# Board_V07A.net
KiCad netlist of a schematic drawn in EAGLE
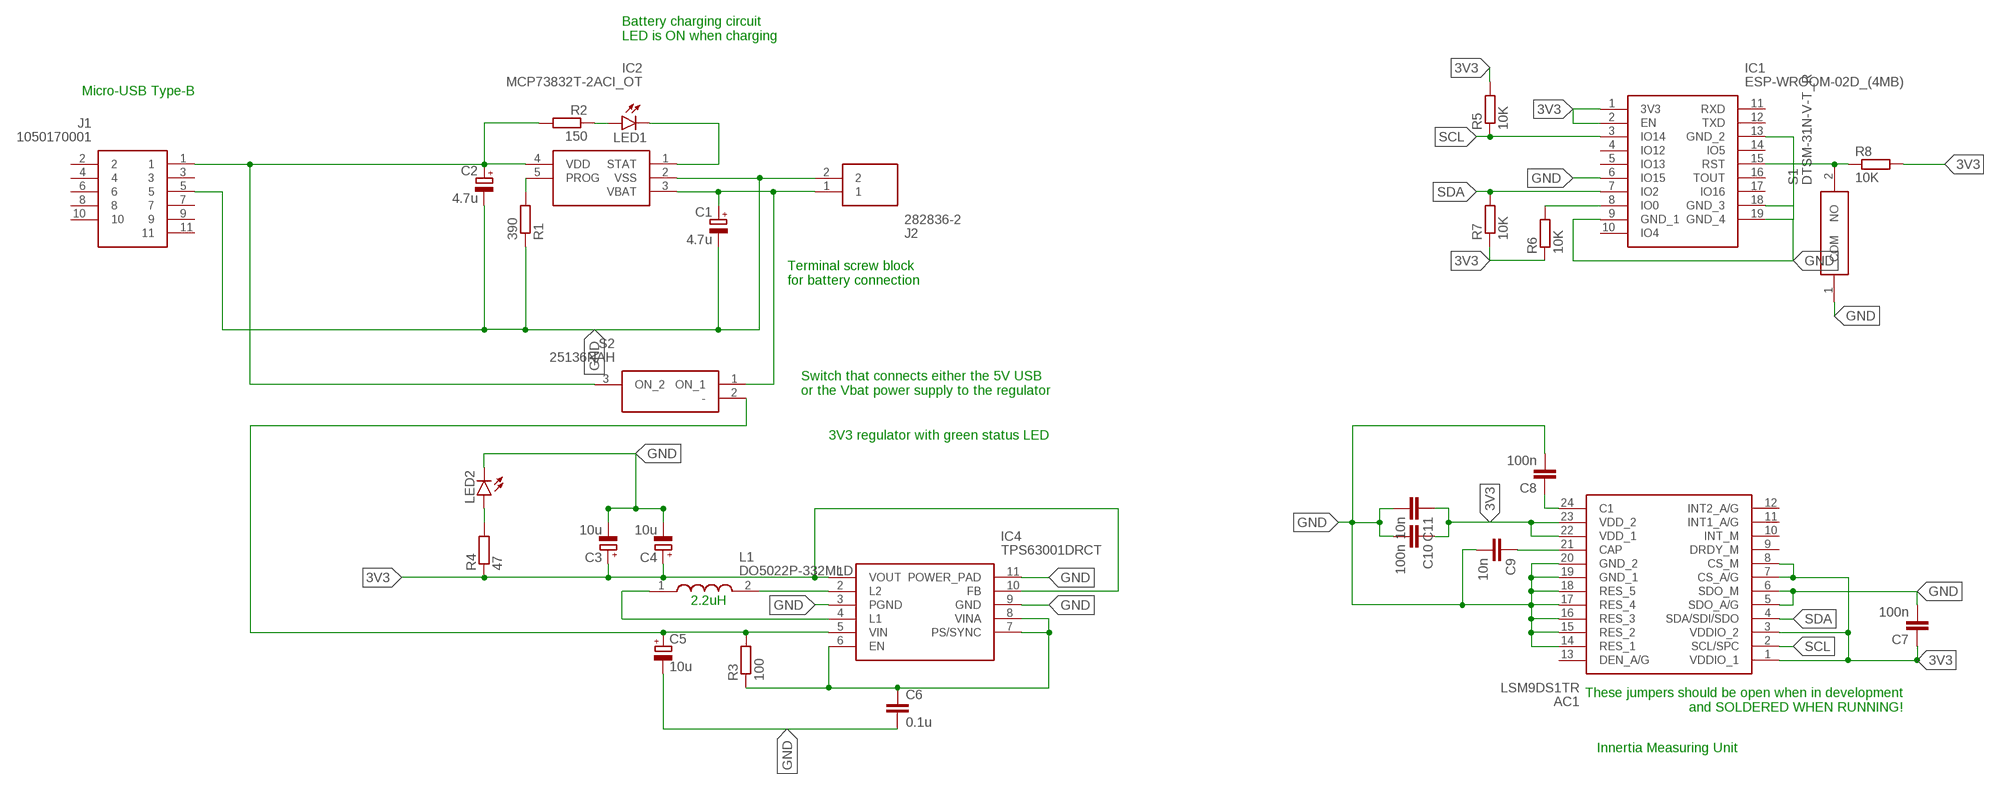
[diagram p0: schematic, sheet 1]

(export (version "E")
  (design (tool "Eeschema 10.0.6"))
  (components
    (comp (ref "AC1")
      (value "LSM9DS1TR")
      (footprint "eagle-import:LGA-24L(3X3.5X1MM)")
      (fields (field (name "MOUSER_PART_NUMBER") "511-LSM9DS1TR") (field (name "RS_PART_NUMBER") "1660908"))
      (libsource (lib "eagle-import") (part "LSM9DS1TR"))
    )
    (comp (ref "C1")
      (value "4.7u")
      (footprint "eagle-import:D_7343-31R")
      (libsource (lib "eagle-import") (part "CPOL-EUD/7343-31R"))
    )
    (comp (ref "C2")
      (value "4.7u")
      (footprint "eagle-import:D_7343-31R")
      (libsource (lib "eagle-import") (part "CPOL-EUD/7343-31R"))
    )
    (comp (ref "C3")
      (value "10u")
      (footprint "eagle-import:D_7343-31R")
      (libsource (lib "eagle-import") (part "CPOL-EUD/7343-31R"))
    )
    (comp (ref "C4")
      (value "10u")
      (footprint "eagle-import:D_7343-31R")
      (libsource (lib "eagle-import") (part "CPOL-EUD/7343-31R"))
    )
    (comp (ref "C5")
      (value "10u")
      (footprint "eagle-import:D_7343-31R")
      (libsource (lib "eagle-import") (part "CPOL-EUD/7343-31R"))
    )
    (comp (ref "C6")
      (value "0.1u")
      (footprint "eagle-import:C0402")
      (libsource (lib "eagle-import") (part "C-EUC0402"))
    )
    (comp (ref "C7")
      (value "100n")
      (footprint "eagle-import:C0805")
      (libsource (lib "eagle-import") (part "C-EUC0805"))
    )
    (comp (ref "C8")
      (value "100n")
      (footprint "eagle-import:C0805")
      (libsource (lib "eagle-import") (part "C-EUC0805"))
    )
    (comp (ref "C9")
      (value "10n")
      (footprint "eagle-import:C0805")
      (libsource (lib "eagle-import") (part "C-EUC0805"))
    )
    (comp (ref "C10")
      (value "100n")
      (footprint "eagle-import:C0805")
      (libsource (lib "eagle-import") (part "C-EUC0805"))
    )
    (comp (ref "C11")
      (value "10n")
      (footprint "eagle-import:C0805")
      (libsource (lib "eagle-import") (part "C-EUC0805"))
    )
    (comp (ref "IC1")
      (value "ESP-WROOM-02D_(4MB)")
      (footprint "eagle-import:ESPWROOM02D")
      (fields
        (field (name "MANUFACTURER_PART_NUMBER") "ESP-WROOM-02D (4MB)")
        (field (name "MOUSER_PART_NUMBER") "356-ESPWROOM02D(4MB)")
      )
      (libsource (lib "eagle-import") (part "ESP-WROOM-02D_(4MB)"))
    )
    (comp (ref "IC2")
      (value "MCP73832T-2ACI_OT")
      (footprint "eagle-import:SOT95P270X145-5N")
      (fields
        (field (name "MANUFACTURER_PART_NUMBER") "MCP73832T-2ACI/OT")
        (field (name "MOUSER_PART_NUMBER") "579-MCP73832T-2ACIOT")
        (field (name "RS_PART_NUMBER") "9122897")
      )
      (libsource (lib "eagle-import") (part "MCP73832T-2ACI_OT"))
    )
    (comp (ref "IC4")
      (value "TPS63001DRCT")
      (footprint "eagle-import:SON50P300X300X100-11N")
      (fields (field (name "RS_PART_NUMBER") "7968405"))
      (libsource (lib "eagle-import") (part "TPS63001DRCT"))
    )
    (comp (ref "J1")
      (value "1050170001")
      (footprint "eagle-import:MICROUSB-BTYPE")
      (libsource (lib "eagle-import") (part "1050170001"))
    )
    (comp (ref "J2")
      (value "282836-2")
      (footprint "eagle-import:SHDR2W100P0X500_1X2_1000X820X1")
      (fields (field (name "MOUSER_PART_NUMBER") "571-2828362") (field (name "RS_PART_NUMBER") "1354983"))
      (libsource (lib "eagle-import") (part "282836-2"))
    )
    (comp (ref "L1")
      (value "DO5022P-332MLD")
      (footprint "eagle-import:DO5022P-104MLD")
      (fields (field (name "MOUSER_PART_NUMBER") "994-DO5022P-332MLD"))
      (libsource (lib "eagle-import") (part "DO5022P-332MLD"))
    )
    (comp (ref "LED1")
      (value "LED5MM")
      (footprint "eagle-import:LED5MM")
      (libsource (lib "eagle-import") (part "LED5MM"))
    )
    (comp (ref "LED2")
      (value "LED5MM")
      (footprint "eagle-import:LED5MM")
      (libsource (lib "eagle-import") (part "LED5MM"))
    )
    (comp (ref "R1")
      (value "390")
      (footprint "eagle-import:R0805")
      (libsource (lib "eagle-import") (part "R-EU_R0805"))
    )
    (comp (ref "R2")
      (value "150")
      (footprint "eagle-import:R0805")
      (libsource (lib "eagle-import") (part "R-EU_R0805"))
    )
    (comp (ref "R3")
      (value "100")
      (footprint "eagle-import:R0805")
      (libsource (lib "eagle-import") (part "R-EU_R0805"))
    )
    (comp (ref "R4")
      (value "47")
      (footprint "eagle-import:R0805")
      (libsource (lib "eagle-import") (part "R-EU_R0805"))
    )
    (comp (ref "R5")
      (value "10K")
      (footprint "eagle-import:R0805")
      (libsource (lib "eagle-import") (part "R-EU_R0805"))
    )
    (comp (ref "R6")
      (value "10K")
      (footprint "eagle-import:R0805")
      (libsource (lib "eagle-import") (part "R-EU_R0805"))
    )
    (comp (ref "R7")
      (value "10K")
      (footprint "eagle-import:R0805")
      (libsource (lib "eagle-import") (part "R-EU_R0805"))
    )
    (comp (ref "R8")
      (value "10K")
      (footprint "eagle-import:R0805")
      (libsource (lib "eagle-import") (part "R-EU_R0805"))
    )
    (comp (ref "S1")
      (value "DTSM-31N-V-T_R")
      (footprint "eagle-import:DTSM32NVTR")
      (fields
        (field (name "MANUFACTURER_PART_NUMBER") "DTSM-31N-V-T/R")
        (field (name "MOUSER_PART_NUMBER") "113-DTSM31NVTR")
      )
      (libsource (lib "eagle-import") (part "DTSM-31N-V-T_R"))
    )
    (comp (ref "S2")
      (value "25136NAH")
      (footprint "eagle-import:25136NAH")
      (fields (field (name "MOUSER_PART_NUMBER") "642-25136NAH") (field (name "RS_PART_NUMBER") "0339673A"))
      (libsource (lib "eagle-import") (part "25136NAH"))
    )
  )
  (nets
    (net (code "1") (name "3V3") (class "Default")
      (node (ref "AC1") (pin "1") (pinfunction "VDDIO_1_1") (pintype "power_in"))
      (node (ref "AC1") (pin "22") (pinfunction "VDD_1_22") (pintype "power_in"))
      (node (ref "AC1") (pin "23") (pinfunction "VDD_2_23") (pintype "power_in"))
      (node (ref "AC1") (pin "3") (pinfunction "VDDIO_2_3") (pintype "power_in"))
      (node (ref "AC1") (pin "7") (pinfunction "CS_A/G_7") (pintype "bidirectional"))
      (node (ref "AC1") (pin "8") (pinfunction "CS_M_8") (pintype "bidirectional"))
      (node (ref "C10") (pin "1") (pinfunction "1_1") (pintype "passive"))
      (node (ref "C11") (pin "1") (pinfunction "1_1") (pintype "passive"))
      (node (ref "C3") (pin "+") (pinfunction "+_+") (pintype "passive"))
      (node (ref "C4") (pin "+") (pinfunction "+_+") (pintype "passive"))
      (node (ref "C7") (pin "1") (pinfunction "1_1") (pintype "passive"))
      (node (ref "IC1") (pin "1") (pinfunction "3V3_1") (pintype "bidirectional"))
      (node (ref "IC1") (pin "2") (pinfunction "EN_2") (pintype "bidirectional"))
      (node (ref "IC4") (pin "1") (pinfunction "VOUT_1") (pintype "bidirectional"))
      (node (ref "IC4") (pin "10") (pinfunction "FB_10") (pintype "bidirectional"))
      (node (ref "R4") (pin "1") (pinfunction "1_1") (pintype "passive"))
      (node (ref "R5") (pin "2") (pinfunction "2_2") (pintype "passive"))
      (node (ref "R6") (pin "1") (pinfunction "1_1") (pintype "passive"))
      (node (ref "R7") (pin "1") (pinfunction "1_1") (pintype "passive"))
      (node (ref "R8") (pin "2") (pinfunction "2_2") (pintype "passive"))
    )
    (net (code "2") (name "GND") (class "Default")
      (node (ref "AC1") (pin "14") (pinfunction "RES_1_14") (pintype "power_in"))
      (node (ref "AC1") (pin "15") (pinfunction "RES_2_15") (pintype "power_in"))
      (node (ref "AC1") (pin "16") (pinfunction "RES_3_16") (pintype "power_in"))
      (node (ref "AC1") (pin "17") (pinfunction "RES_4_17") (pintype "power_in"))
      (node (ref "AC1") (pin "18") (pinfunction "RES_5_18") (pintype "power_in"))
      (node (ref "AC1") (pin "19") (pinfunction "GND_1_19") (pintype "power_in"))
      (node (ref "AC1") (pin "20") (pinfunction "GND_2_20") (pintype "power_in"))
      (node (ref "AC1") (pin "5") (pinfunction "SDO_A/G_5") (pintype "output"))
      (node (ref "AC1") (pin "6") (pinfunction "SDO_M_6") (pintype "output"))
      (node (ref "C1") (pin "-") (pinfunction "-_-") (pintype "passive"))
      (node (ref "C10") (pin "2") (pinfunction "2_2") (pintype "passive"))
      (node (ref "C11") (pin "2") (pinfunction "2_2") (pintype "passive"))
      (node (ref "C2") (pin "-") (pinfunction "-_-") (pintype "passive"))
      (node (ref "C3") (pin "-") (pinfunction "-_-") (pintype "passive"))
      (node (ref "C4") (pin "-") (pinfunction "-_-") (pintype "passive"))
      (node (ref "C5") (pin "-") (pinfunction "-_-") (pintype "passive"))
      (node (ref "C6") (pin "2") (pinfunction "2_2") (pintype "passive"))
      (node (ref "C7") (pin "2") (pinfunction "2_2") (pintype "passive"))
      (node (ref "C8") (pin "2") (pinfunction "2_2") (pintype "passive"))
      (node (ref "C9") (pin "2") (pinfunction "2_2") (pintype "passive"))
      (node (ref "IC1") (pin "13") (pinfunction "GND_2_13") (pintype "bidirectional"))
      (node (ref "IC1") (pin "18") (pinfunction "GND_3_18") (pintype "bidirectional"))
      (node (ref "IC1") (pin "19") (pinfunction "GND_4_19") (pintype "bidirectional"))
      (node (ref "IC1") (pin "6") (pinfunction "IO15_6") (pintype "bidirectional"))
      (node (ref "IC1") (pin "9") (pinfunction "GND_1_9") (pintype "bidirectional"))
      (node (ref "IC2") (pin "2") (pinfunction "VSS_2") (pintype "power_in"))
      (node (ref "IC4") (pin "11") (pinfunction "POWER_PAD_11") (pintype "bidirectional"))
      (node (ref "IC4") (pin "3") (pinfunction "PGND_3") (pintype "bidirectional"))
      (node (ref "IC4") (pin "9") (pinfunction "GND_9") (pintype "bidirectional"))
      (node (ref "J1") (pin "5") (pinfunction "5_5") (pintype "bidirectional"))
      (node (ref "J2") (pin "2") (pinfunction "2_2") (pintype "bidirectional"))
      (node (ref "LED2") (pin "K") (pinfunction "C_K") (pintype "passive"))
      (node (ref "R1") (pin "1") (pinfunction "1_1") (pintype "passive"))
      (node (ref "S1") (pin "1") (pinfunction "COM_1") (pintype "bidirectional"))
    )
    (net (code "3") (name "Net-(AC1-C1)") (class "Default")
      (node (ref "AC1") (pin "24") (pinfunction "C1_24") (pintype "bidirectional"))
      (node (ref "C8") (pin "1") (pinfunction "1_1") (pintype "passive"))
    )
    (net (code "4") (name "Net-(AC1-CAP)") (class "Default")
      (node (ref "AC1") (pin "21") (pinfunction "CAP_21") (pintype "power_in"))
      (node (ref "C9") (pin "1") (pinfunction "1_1") (pintype "passive"))
    )
    (net (code "5") (name "Net-(IC1-IO0)") (class "Default")
      (node (ref "IC1") (pin "8") (pinfunction "IO0_8") (pintype "bidirectional"))
      (node (ref "R6") (pin "2") (pinfunction "2_2") (pintype "passive"))
    )
    (net (code "6") (name "Net-(IC1-RST)") (class "Default")
      (node (ref "IC1") (pin "15") (pinfunction "RST_15") (pintype "bidirectional"))
      (node (ref "R8") (pin "1") (pinfunction "1_1") (pintype "passive"))
      (node (ref "S1") (pin "2") (pinfunction "NO_2") (pintype "bidirectional"))
    )
    (net (code "7") (name "Net-(IC2-PROG)") (class "Default")
      (node (ref "IC2") (pin "5") (pinfunction "PROG_5") (pintype "bidirectional"))
      (node (ref "R1") (pin "2") (pinfunction "2_2") (pintype "passive"))
    )
    (net (code "8") (name "Net-(IC2-STAT)") (class "Default")
      (node (ref "IC2") (pin "1") (pinfunction "STAT_1") (pintype "bidirectional"))
      (node (ref "LED1") (pin "K") (pinfunction "C_K") (pintype "passive"))
    )
    (net (code "9") (name "Net-(IC2-VBAT)") (class "Default")
      (node (ref "C1") (pin "+") (pinfunction "+_+") (pintype "passive"))
      (node (ref "IC2") (pin "3") (pinfunction "VBAT_3") (pintype "bidirectional"))
      (node (ref "J2") (pin "1") (pinfunction "1_1") (pintype "bidirectional"))
      (node (ref "S2") (pin "1") (pinfunction "ON_1_1") (pintype "bidirectional"))
    )
    (net (code "10") (name "Net-(IC2-VDD)") (class "Default")
      (node (ref "C2") (pin "+") (pinfunction "+_+") (pintype "passive"))
      (node (ref "IC2") (pin "4") (pinfunction "VDD_4") (pintype "power_in"))
      (node (ref "J1") (pin "1") (pinfunction "1_1") (pintype "bidirectional"))
      (node (ref "R2") (pin "2") (pinfunction "2_2") (pintype "passive"))
      (node (ref "S2") (pin "3") (pinfunction "ON_2_3") (pintype "bidirectional"))
    )
    (net (code "11") (name "Net-(IC4-EN)") (class "Default")
      (node (ref "C6") (pin "1") (pinfunction "1_1") (pintype "passive"))
      (node (ref "IC4") (pin "6") (pinfunction "EN_6") (pintype "bidirectional"))
      (node (ref "IC4") (pin "7") (pinfunction "PS/SYNC_7") (pintype "bidirectional"))
      (node (ref "IC4") (pin "8") (pinfunction "VINA_8") (pintype "bidirectional"))
      (node (ref "R3") (pin "1") (pinfunction "1_1") (pintype "passive"))
    )
    (net (code "12") (name "Net-(IC4-L1)") (class "Default")
      (node (ref "IC4") (pin "4") (pinfunction "L1_4") (pintype "bidirectional"))
      (node (ref "L1") (pin "1") (pinfunction "1_1") (pintype "bidirectional"))
    )
    (net (code "13") (name "Net-(IC4-L2)") (class "Default")
      (node (ref "IC4") (pin "2") (pinfunction "L2_2") (pintype "bidirectional"))
      (node (ref "L1") (pin "2") (pinfunction "2_2") (pintype "bidirectional"))
    )
    (net (code "14") (name "Net-(IC4-VIN)") (class "Default")
      (node (ref "C5") (pin "+") (pinfunction "+_+") (pintype "passive"))
      (node (ref "IC4") (pin "5") (pinfunction "VIN_5") (pintype "bidirectional"))
      (node (ref "R3") (pin "2") (pinfunction "2_2") (pintype "passive"))
      (node (ref "S2") (pin "2") (pinfunction "-_2") (pintype "bidirectional"))
    )
    (net (code "15") (name "Net-(LED1-PadA)") (class "Default")
      (node (ref "LED1") (pin "A") (pinfunction "A_A") (pintype "passive"))
      (node (ref "R2") (pin "1") (pinfunction "1_1") (pintype "passive"))
    )
    (net (code "16") (name "Net-(LED2-PadA)") (class "Default")
      (node (ref "LED2") (pin "A") (pinfunction "A_A") (pintype "passive"))
      (node (ref "R4") (pin "2") (pinfunction "2_2") (pintype "passive"))
    )
    (net (code "17") (name "SCL") (class "Default")
      (node (ref "AC1") (pin "2") (pinfunction "SCL/SPC_2") (pintype "output"))
      (node (ref "IC1") (pin "3") (pinfunction "IO14_3") (pintype "bidirectional"))
      (node (ref "R5") (pin "1") (pinfunction "1_1") (pintype "passive"))
    )
    (net (code "18") (name "SDA") (class "Default")
      (node (ref "AC1") (pin "4") (pinfunction "SDA/SDI/SDO_4") (pintype "bidirectional"))
      (node (ref "IC1") (pin "7") (pinfunction "IO2_7") (pintype "bidirectional"))
      (node (ref "R7") (pin "2") (pinfunction "2_2") (pintype "passive"))
    )
    (net (code "19") (name "unconnected-(AC1-DEN_A{slash}G-Pad13)") (class "Default")
      (node (ref "AC1") (pin "13") (pinfunction "DEN_A/G_13") (pintype "bidirectional"))
    )
    (net (code "20") (name "unconnected-(AC1-DRDY_M-Pad9)") (class "Default")
      (node (ref "AC1") (pin "9") (pinfunction "DRDY_M_9") (pintype "bidirectional"))
    )
    (net (code "21") (name "unconnected-(AC1-INT1_A{slash}G-Pad11)") (class "Default")
      (node (ref "AC1") (pin "11") (pinfunction "INT1_A/G_11") (pintype "bidirectional"))
    )
    (net (code "22") (name "unconnected-(AC1-INT2_A{slash}G-Pad12)") (class "Default")
      (node (ref "AC1") (pin "12") (pinfunction "INT2_A/G_12") (pintype "bidirectional"))
    )
    (net (code "23") (name "unconnected-(AC1-INT_M-Pad10)") (class "Default")
      (node (ref "AC1") (pin "10") (pinfunction "INT_M_10") (pintype "bidirectional"))
    )
    (net (code "24") (name "unconnected-(IC1-IO4-Pad10)") (class "Default")
      (node (ref "IC1") (pin "10") (pinfunction "IO4_10") (pintype "bidirectional"))
    )
    (net (code "25") (name "unconnected-(IC1-IO5-Pad14)") (class "Default")
      (node (ref "IC1") (pin "14") (pinfunction "IO5_14") (pintype "bidirectional"))
    )
    (net (code "26") (name "unconnected-(IC1-IO12-Pad4)") (class "Default")
      (node (ref "IC1") (pin "4") (pinfunction "IO12_4") (pintype "bidirectional"))
    )
    (net (code "27") (name "unconnected-(IC1-IO13-Pad5)") (class "Default")
      (node (ref "IC1") (pin "5") (pinfunction "IO13_5") (pintype "bidirectional"))
    )
    (net (code "28") (name "unconnected-(IC1-IO16-Pad17)") (class "Default")
      (node (ref "IC1") (pin "17") (pinfunction "IO16_17") (pintype "bidirectional"))
    )
    (net (code "29") (name "unconnected-(IC1-RXD-Pad11)") (class "Default")
      (node (ref "IC1") (pin "11") (pinfunction "RXD_11") (pintype "bidirectional"))
    )
    (net (code "30") (name "unconnected-(IC1-TOUT-Pad16)") (class "Default")
      (node (ref "IC1") (pin "16") (pinfunction "TOUT_16") (pintype "bidirectional"))
    )
    (net (code "31") (name "unconnected-(IC1-TXD-Pad12)") (class "Default")
      (node (ref "IC1") (pin "12") (pinfunction "TXD_12") (pintype "bidirectional"))
    )
    (net (code "32") (name "unconnected-(J1-Pad2)") (class "Default")
      (node (ref "J1") (pin "2") (pinfunction "2_2") (pintype "bidirectional"))
    )
    (net (code "33") (name "unconnected-(J1-Pad3)") (class "Default")
      (node (ref "J1") (pin "3") (pinfunction "3_3") (pintype "bidirectional"))
    )
    (net (code "34") (name "unconnected-(J1-Pad4)") (class "Default")
      (node (ref "J1") (pin "4") (pinfunction "4_4") (pintype "bidirectional"))
    )
    (net (code "35") (name "unconnected-(J1-Pad6)") (class "Default")
      (node (ref "J1") (pin "6") (pinfunction "6_6") (pintype "bidirectional"))
    )
    (net (code "36") (name "unconnected-(J1-Pad7)") (class "Default")
      (node (ref "J1") (pin "7") (pinfunction "7_7") (pintype "bidirectional"))
    )
    (net (code "37") (name "unconnected-(J1-Pad8)") (class "Default")
      (node (ref "J1") (pin "8") (pinfunction "8_8") (pintype "bidirectional"))
    )
    (net (code "38") (name "unconnected-(J1-Pad9)") (class "Default")
      (node (ref "J1") (pin "9") (pinfunction "9_9") (pintype "bidirectional"))
    )
    (net (code "39") (name "unconnected-(J1-Pad10)") (class "Default")
      (node (ref "J1") (pin "10") (pinfunction "10_10") (pintype "bidirectional"))
    )
    (net (code "40") (name "unconnected-(J1-Pad11)") (class "Default")
      (node (ref "J1") (pin "11") (pinfunction "11_11") (pintype "bidirectional"))
    )
  )
)
